# Connector.net
KiCad netlist of a schematic drawn in Altium Designer
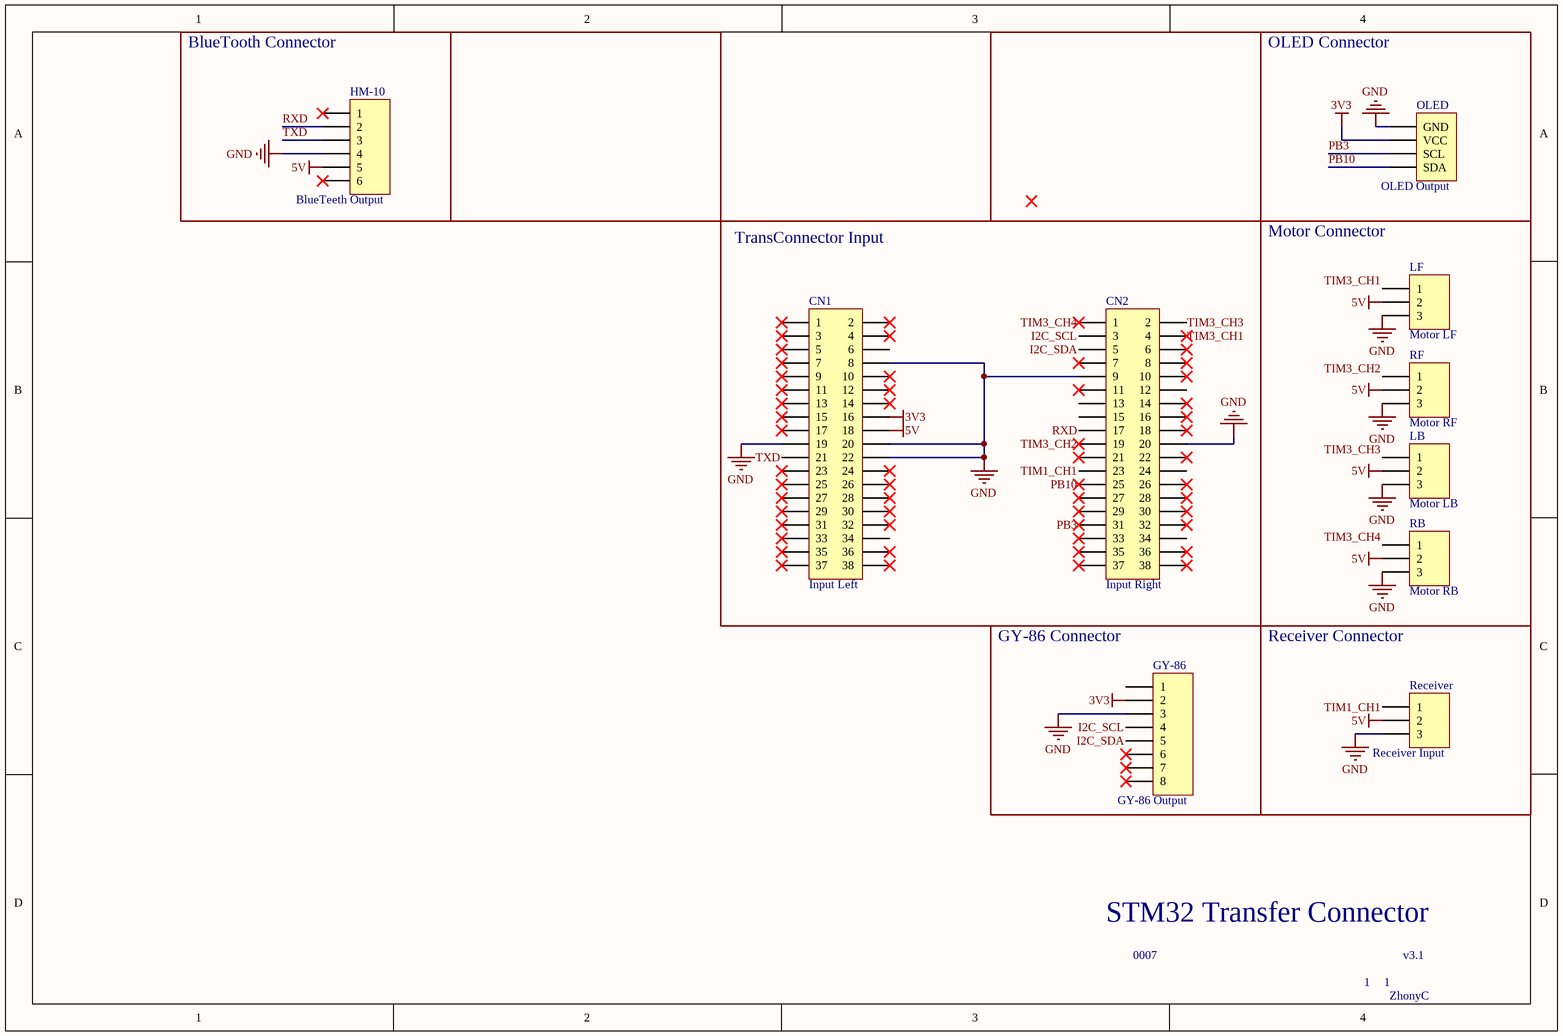
[diagram p0: Connector.SchDoc]

(export (version "E")
  (design (tool "Eeschema 10.0.6"))
  (components
    (comp (ref "CN1")
      (value "Input Left")
      (footprint "2*19P")
      (description "Header, 19-Pin, Dual row")
      (fields (field (name "PUBLISHER") "Altium Limited"))
      (libsource (lib "Miscellaneous Connectors") (part "Header 19X2"))
    )
    (comp (ref "CN2")
      (value "Input Right")
      (footprint "2*19P")
      (description "Header, 19-Pin, Dual row")
      (fields (field (name "PUBLISHER") "Altium Limited"))
      (libsource (lib "Miscellaneous Connectors") (part "Header 19X2"))
    )
    (comp (ref "GY-86")
      (value "GY-86 Output")
      (footprint "HDR1X8")
      (description "Header, 8-Pin")
      (fields (field (name "PUBLISHER") "Altium Limited"))
      (libsource (lib "Miscellaneous Connectors") (part "Header 8"))
    )
    (comp (ref "HM-10")
      (value "BlueTeeth Output")
      (footprint "HDR1X6")
      (description "Header, 6-Pin")
      (fields (field (name "PUBLISHER") "Altium Limited"))
      (libsource (lib "Miscellaneous Connectors") (part "Header 6"))
    )
    (comp (ref "LB")
      (value "Motor LB")
      (footprint "HDR1X3")
      (description "Header, 3-Pin")
      (fields (field (name "PUBLISHER") "Altium Limited"))
      (libsource (lib "Miscellaneous Connectors") (part "Header 3"))
    )
    (comp (ref "LF")
      (value "Motor LF")
      (footprint "HDR1X3")
      (description "Header, 3-Pin")
      (fields (field (name "PUBLISHER") "Altium Limited"))
      (libsource (lib "Miscellaneous Connectors") (part "Header 3"))
    )
    (comp (ref "OLED")
      (value "OLED Output")
      (footprint "HDR1X4")
      (description "Header, 4-Pin")
      (fields (field (name "PUBLISHER") "Altium Limited"))
      (libsource (lib "Miscellaneous Connectors") (part "Header 4"))
    )
    (comp (ref "RB")
      (value "Motor RB")
      (footprint "HDR1X3")
      (description "Header, 3-Pin")
      (fields (field (name "PUBLISHER") "Altium Limited"))
      (libsource (lib "Miscellaneous Connectors") (part "Header 3"))
    )
    (comp (ref "Receiver")
      (value "Receiver Input")
      (footprint "HDR1X3")
      (description "Header, 3-Pin")
      (fields (field (name "PUBLISHER") "Altium Limited"))
      (libsource (lib "Miscellaneous Connectors") (part "Header 3"))
    )
    (comp (ref "RF")
      (value "Motor RF")
      (footprint "HDR1X3")
      (description "Header, 3-Pin")
      (fields (field (name "PUBLISHER") "Altium Limited"))
      (libsource (lib "Miscellaneous Connectors") (part "Header 3"))
    )
  )
  (nets
    (net (code "1") (name "/I2C_SCL") (class "Default")
      (node (ref "CN2") (pin "3") (pinfunction "3_3") (pintype "passive"))
      (node (ref "GY-86") (pin "4") (pinfunction "4_4") (pintype "passive"))
    )
    (net (code "2") (name "/I2C_SDA") (class "Default")
      (node (ref "CN2") (pin "5") (pinfunction "5_5") (pintype "passive"))
      (node (ref "GY-86") (pin "5") (pinfunction "5_5") (pintype "passive"))
    )
    (net (code "3") (name "/PB3") (class "Default")
      (node (ref "CN2") (pin "31") (pinfunction "31_31") (pintype "passive"))
      (node (ref "OLED") (pin "3") (pinfunction "SCL_3") (pintype "passive"))
    )
    (net (code "4") (name "/PB10") (class "Default")
      (node (ref "CN2") (pin "25") (pinfunction "25_25") (pintype "passive"))
      (node (ref "OLED") (pin "4") (pinfunction "SDA_4") (pintype "passive"))
    )
    (net (code "5") (name "/RXD") (class "Default")
      (node (ref "CN2") (pin "17") (pinfunction "17_17") (pintype "passive"))
      (node (ref "HM-10") (pin "2") (pinfunction "2_2") (pintype "passive"))
    )
    (net (code "6") (name "/TIM1_CH1") (class "Default")
      (node (ref "CN2") (pin "23") (pinfunction "23_23") (pintype "passive"))
      (node (ref "Receiver") (pin "1") (pinfunction "1_1") (pintype "passive"))
    )
    (net (code "7") (name "/TIM3_CH1") (class "Default")
      (node (ref "CN2") (pin "4") (pinfunction "4_4") (pintype "passive"))
      (node (ref "LF") (pin "1") (pinfunction "1_1") (pintype "passive"))
    )
    (net (code "8") (name "/TIM3_CH2") (class "Default")
      (node (ref "CN2") (pin "19") (pinfunction "19_19") (pintype "passive"))
      (node (ref "RF") (pin "1") (pinfunction "1_1") (pintype "passive"))
    )
    (net (code "9") (name "/TIM3_CH3") (class "Default")
      (node (ref "CN2") (pin "2") (pinfunction "2_2") (pintype "passive"))
      (node (ref "LB") (pin "1") (pinfunction "1_1") (pintype "passive"))
    )
    (net (code "10") (name "/TIM3_CH4") (class "Default")
      (node (ref "CN2") (pin "1") (pinfunction "1_1") (pintype "passive"))
      (node (ref "RB") (pin "1") (pinfunction "1_1") (pintype "passive"))
    )
    (net (code "11") (name "/TXD") (class "Default")
      (node (ref "CN1") (pin "21") (pinfunction "21_21") (pintype "passive"))
      (node (ref "HM-10") (pin "3") (pinfunction "3_3") (pintype "passive"))
    )
    (net (code "12") (name "3V3") (class "Default")
      (node (ref "CN1") (pin "16") (pinfunction "16_16") (pintype "passive"))
      (node (ref "GY-86") (pin "2") (pinfunction "2_2") (pintype "passive"))
      (node (ref "OLED") (pin "2") (pinfunction "VCC_2") (pintype "passive"))
    )
    (net (code "13") (name "5V") (class "Default")
      (node (ref "CN1") (pin "18") (pinfunction "18_18") (pintype "passive"))
      (node (ref "HM-10") (pin "5") (pinfunction "5_5") (pintype "passive"))
      (node (ref "LB") (pin "2") (pinfunction "2_2") (pintype "passive"))
      (node (ref "LF") (pin "2") (pinfunction "2_2") (pintype "passive"))
      (node (ref "RB") (pin "2") (pinfunction "2_2") (pintype "passive"))
      (node (ref "RF") (pin "2") (pinfunction "2_2") (pintype "passive"))
      (node (ref "Receiver") (pin "2") (pinfunction "2_2") (pintype "passive"))
    )
    (net (code "14") (name "GND") (class "Default")
      (node (ref "CN1") (pin "19") (pinfunction "19_19") (pintype "passive"))
      (node (ref "CN1") (pin "20") (pinfunction "20_20") (pintype "passive"))
      (node (ref "CN1") (pin "22") (pinfunction "22_22") (pintype "passive"))
      (node (ref "CN1") (pin "8") (pinfunction "8_8") (pintype "passive"))
      (node (ref "CN2") (pin "20") (pinfunction "20_20") (pintype "passive"))
      (node (ref "CN2") (pin "9") (pinfunction "9_9") (pintype "passive"))
      (node (ref "GY-86") (pin "3") (pinfunction "3_3") (pintype "passive"))
      (node (ref "HM-10") (pin "4") (pinfunction "4_4") (pintype "passive"))
      (node (ref "LB") (pin "3") (pinfunction "3_3") (pintype "passive"))
      (node (ref "LF") (pin "3") (pinfunction "3_3") (pintype "passive"))
      (node (ref "OLED") (pin "1") (pinfunction "GND_1") (pintype "passive"))
      (node (ref "RB") (pin "3") (pinfunction "3_3") (pintype "passive"))
      (node (ref "RF") (pin "3") (pinfunction "3_3") (pintype "passive"))
      (node (ref "Receiver") (pin "3") (pinfunction "3_3") (pintype "passive"))
    )
    (net (code "15") (name "unconnected-(CN1-Pad1)") (class "Default")
      (node (ref "CN1") (pin "1") (pinfunction "1_1") (pintype "passive+no_connect"))
    )
    (net (code "16") (name "unconnected-(CN1-Pad2)") (class "Default")
      (node (ref "CN1") (pin "2") (pinfunction "2_2") (pintype "passive+no_connect"))
    )
    (net (code "17") (name "unconnected-(CN1-Pad3)") (class "Default")
      (node (ref "CN1") (pin "3") (pinfunction "3_3") (pintype "passive+no_connect"))
    )
    (net (code "18") (name "unconnected-(CN1-Pad4)") (class "Default")
      (node (ref "CN1") (pin "4") (pinfunction "4_4") (pintype "passive+no_connect"))
    )
    (net (code "19") (name "unconnected-(CN1-Pad5)") (class "Default")
      (node (ref "CN1") (pin "5") (pinfunction "5_5") (pintype "passive+no_connect"))
    )
    (net (code "20") (name "unconnected-(CN1-Pad6)") (class "Default")
      (node (ref "CN1") (pin "6") (pinfunction "6_6") (pintype "passive"))
    )
    (net (code "21") (name "unconnected-(CN1-Pad7)") (class "Default")
      (node (ref "CN1") (pin "7") (pinfunction "7_7") (pintype "passive+no_connect"))
    )
    (net (code "22") (name "unconnected-(CN1-Pad9)") (class "Default")
      (node (ref "CN1") (pin "9") (pinfunction "9_9") (pintype "passive+no_connect"))
    )
    (net (code "23") (name "unconnected-(CN1-Pad10)") (class "Default")
      (node (ref "CN1") (pin "10") (pinfunction "10_10") (pintype "passive+no_connect"))
    )
    (net (code "24") (name "unconnected-(CN1-Pad11)") (class "Default")
      (node (ref "CN1") (pin "11") (pinfunction "11_11") (pintype "passive+no_connect"))
    )
    (net (code "25") (name "unconnected-(CN1-Pad12)") (class "Default")
      (node (ref "CN1") (pin "12") (pinfunction "12_12") (pintype "passive+no_connect"))
    )
    (net (code "26") (name "unconnected-(CN1-Pad13)") (class "Default")
      (node (ref "CN1") (pin "13") (pinfunction "13_13") (pintype "passive+no_connect"))
    )
    (net (code "27") (name "unconnected-(CN1-Pad14)") (class "Default")
      (node (ref "CN1") (pin "14") (pinfunction "14_14") (pintype "passive+no_connect"))
    )
    (net (code "28") (name "unconnected-(CN1-Pad15)") (class "Default")
      (node (ref "CN1") (pin "15") (pinfunction "15_15") (pintype "passive+no_connect"))
    )
    (net (code "29") (name "unconnected-(CN1-Pad17)") (class "Default")
      (node (ref "CN1") (pin "17") (pinfunction "17_17") (pintype "passive+no_connect"))
    )
    (net (code "30") (name "unconnected-(CN1-Pad23)") (class "Default")
      (node (ref "CN1") (pin "23") (pinfunction "23_23") (pintype "passive+no_connect"))
    )
    (net (code "31") (name "unconnected-(CN1-Pad24)") (class "Default")
      (node (ref "CN1") (pin "24") (pinfunction "24_24") (pintype "passive+no_connect"))
    )
    (net (code "32") (name "unconnected-(CN1-Pad25)") (class "Default")
      (node (ref "CN1") (pin "25") (pinfunction "25_25") (pintype "passive+no_connect"))
    )
    (net (code "33") (name "unconnected-(CN1-Pad26)") (class "Default")
      (node (ref "CN1") (pin "26") (pinfunction "26_26") (pintype "passive+no_connect"))
    )
    (net (code "34") (name "unconnected-(CN1-Pad27)") (class "Default")
      (node (ref "CN1") (pin "27") (pinfunction "27_27") (pintype "passive+no_connect"))
    )
    (net (code "35") (name "unconnected-(CN1-Pad28)") (class "Default")
      (node (ref "CN1") (pin "28") (pinfunction "28_28") (pintype "passive+no_connect"))
    )
    (net (code "36") (name "unconnected-(CN1-Pad29)") (class "Default")
      (node (ref "CN1") (pin "29") (pinfunction "29_29") (pintype "passive+no_connect"))
    )
    (net (code "37") (name "unconnected-(CN1-Pad30)") (class "Default")
      (node (ref "CN1") (pin "30") (pinfunction "30_30") (pintype "passive+no_connect"))
    )
    (net (code "38") (name "unconnected-(CN1-Pad31)") (class "Default")
      (node (ref "CN1") (pin "31") (pinfunction "31_31") (pintype "passive+no_connect"))
    )
    (net (code "39") (name "unconnected-(CN1-Pad32)") (class "Default")
      (node (ref "CN1") (pin "32") (pinfunction "32_32") (pintype "passive+no_connect"))
    )
    (net (code "40") (name "unconnected-(CN1-Pad33)") (class "Default")
      (node (ref "CN1") (pin "33") (pinfunction "33_33") (pintype "passive+no_connect"))
    )
    (net (code "41") (name "unconnected-(CN1-Pad34)") (class "Default")
      (node (ref "CN1") (pin "34") (pinfunction "34_34") (pintype "passive"))
    )
    (net (code "42") (name "unconnected-(CN1-Pad35)") (class "Default")
      (node (ref "CN1") (pin "35") (pinfunction "35_35") (pintype "passive+no_connect"))
    )
    (net (code "43") (name "unconnected-(CN1-Pad36)") (class "Default")
      (node (ref "CN1") (pin "36") (pinfunction "36_36") (pintype "passive+no_connect"))
    )
    (net (code "44") (name "unconnected-(CN1-Pad37)") (class "Default")
      (node (ref "CN1") (pin "37") (pinfunction "37_37") (pintype "passive+no_connect"))
    )
    (net (code "45") (name "unconnected-(CN1-Pad38)") (class "Default")
      (node (ref "CN1") (pin "38") (pinfunction "38_38") (pintype "passive+no_connect"))
    )
    (net (code "46") (name "unconnected-(CN2-Pad6)") (class "Default")
      (node (ref "CN2") (pin "6") (pinfunction "6_6") (pintype "passive+no_connect"))
    )
    (net (code "47") (name "unconnected-(CN2-Pad7)") (class "Default")
      (node (ref "CN2") (pin "7") (pinfunction "7_7") (pintype "passive+no_connect"))
    )
    (net (code "48") (name "unconnected-(CN2-Pad8)") (class "Default")
      (node (ref "CN2") (pin "8") (pinfunction "8_8") (pintype "passive+no_connect"))
    )
    (net (code "49") (name "unconnected-(CN2-Pad10)") (class "Default")
      (node (ref "CN2") (pin "10") (pinfunction "10_10") (pintype "passive+no_connect"))
    )
    (net (code "50") (name "unconnected-(CN2-Pad11)") (class "Default")
      (node (ref "CN2") (pin "11") (pinfunction "11_11") (pintype "passive+no_connect"))
    )
    (net (code "51") (name "unconnected-(CN2-Pad12)") (class "Default")
      (node (ref "CN2") (pin "12") (pinfunction "12_12") (pintype "passive"))
    )
    (net (code "52") (name "unconnected-(CN2-Pad13)") (class "Default")
      (node (ref "CN2") (pin "13") (pinfunction "13_13") (pintype "passive"))
    )
    (net (code "53") (name "unconnected-(CN2-Pad14)") (class "Default")
      (node (ref "CN2") (pin "14") (pinfunction "14_14") (pintype "passive+no_connect"))
    )
    (net (code "54") (name "unconnected-(CN2-Pad15)") (class "Default")
      (node (ref "CN2") (pin "15") (pinfunction "15_15") (pintype "passive"))
    )
    (net (code "55") (name "unconnected-(CN2-Pad16)") (class "Default")
      (node (ref "CN2") (pin "16") (pinfunction "16_16") (pintype "passive+no_connect"))
    )
    (net (code "56") (name "unconnected-(CN2-Pad18)") (class "Default")
      (node (ref "CN2") (pin "18") (pinfunction "18_18") (pintype "passive+no_connect"))
    )
    (net (code "57") (name "unconnected-(CN2-Pad21)") (class "Default")
      (node (ref "CN2") (pin "21") (pinfunction "21_21") (pintype "passive+no_connect"))
    )
    (net (code "58") (name "unconnected-(CN2-Pad22)") (class "Default")
      (node (ref "CN2") (pin "22") (pinfunction "22_22") (pintype "passive+no_connect"))
    )
    (net (code "59") (name "unconnected-(CN2-Pad24)") (class "Default")
      (node (ref "CN2") (pin "24") (pinfunction "24_24") (pintype "passive"))
    )
    (net (code "60") (name "unconnected-(CN2-Pad26)") (class "Default")
      (node (ref "CN2") (pin "26") (pinfunction "26_26") (pintype "passive+no_connect"))
    )
    (net (code "61") (name "unconnected-(CN2-Pad27)") (class "Default")
      (node (ref "CN2") (pin "27") (pinfunction "27_27") (pintype "passive+no_connect"))
    )
    (net (code "62") (name "unconnected-(CN2-Pad28)") (class "Default")
      (node (ref "CN2") (pin "28") (pinfunction "28_28") (pintype "passive+no_connect"))
    )
    (net (code "63") (name "unconnected-(CN2-Pad29)") (class "Default")
      (node (ref "CN2") (pin "29") (pinfunction "29_29") (pintype "passive+no_connect"))
    )
    (net (code "64") (name "unconnected-(CN2-Pad30)") (class "Default")
      (node (ref "CN2") (pin "30") (pinfunction "30_30") (pintype "passive+no_connect"))
    )
    (net (code "65") (name "unconnected-(CN2-Pad32)") (class "Default")
      (node (ref "CN2") (pin "32") (pinfunction "32_32") (pintype "passive+no_connect"))
    )
    (net (code "66") (name "unconnected-(CN2-Pad33)") (class "Default")
      (node (ref "CN2") (pin "33") (pinfunction "33_33") (pintype "passive+no_connect"))
    )
    (net (code "67") (name "unconnected-(CN2-Pad34)") (class "Default")
      (node (ref "CN2") (pin "34") (pinfunction "34_34") (pintype "passive"))
    )
    (net (code "68") (name "unconnected-(CN2-Pad35)") (class "Default")
      (node (ref "CN2") (pin "35") (pinfunction "35_35") (pintype "passive+no_connect"))
    )
    (net (code "69") (name "unconnected-(CN2-Pad36)") (class "Default")
      (node (ref "CN2") (pin "36") (pinfunction "36_36") (pintype "passive+no_connect"))
    )
    (net (code "70") (name "unconnected-(CN2-Pad37)") (class "Default")
      (node (ref "CN2") (pin "37") (pinfunction "37_37") (pintype "passive+no_connect"))
    )
    (net (code "71") (name "unconnected-(CN2-Pad38)") (class "Default")
      (node (ref "CN2") (pin "38") (pinfunction "38_38") (pintype "passive+no_connect"))
    )
    (net (code "72") (name "unconnected-(GY-86-Pad1)") (class "Default")
      (node (ref "GY-86") (pin "1") (pinfunction "1_1") (pintype "passive"))
    )
    (net (code "73") (name "unconnected-(GY-86-Pad6)") (class "Default")
      (node (ref "GY-86") (pin "6") (pinfunction "6_6") (pintype "passive+no_connect"))
    )
    (net (code "74") (name "unconnected-(GY-86-Pad7)") (class "Default")
      (node (ref "GY-86") (pin "7") (pinfunction "7_7") (pintype "passive+no_connect"))
    )
    (net (code "75") (name "unconnected-(GY-86-Pad8)") (class "Default")
      (node (ref "GY-86") (pin "8") (pinfunction "8_8") (pintype "passive+no_connect"))
    )
    (net (code "76") (name "unconnected-(HM-10-Pad1)") (class "Default")
      (node (ref "HM-10") (pin "1") (pinfunction "1_1") (pintype "passive+no_connect"))
    )
    (net (code "77") (name "unconnected-(HM-10-Pad6)") (class "Default")
      (node (ref "HM-10") (pin "6") (pinfunction "6_6") (pintype "passive+no_connect"))
    )
  )
)
